# SCH_Motor-Driver-Pcb_2024-06-14.net
KiCad netlist of a schematic drawn in EasyEDA
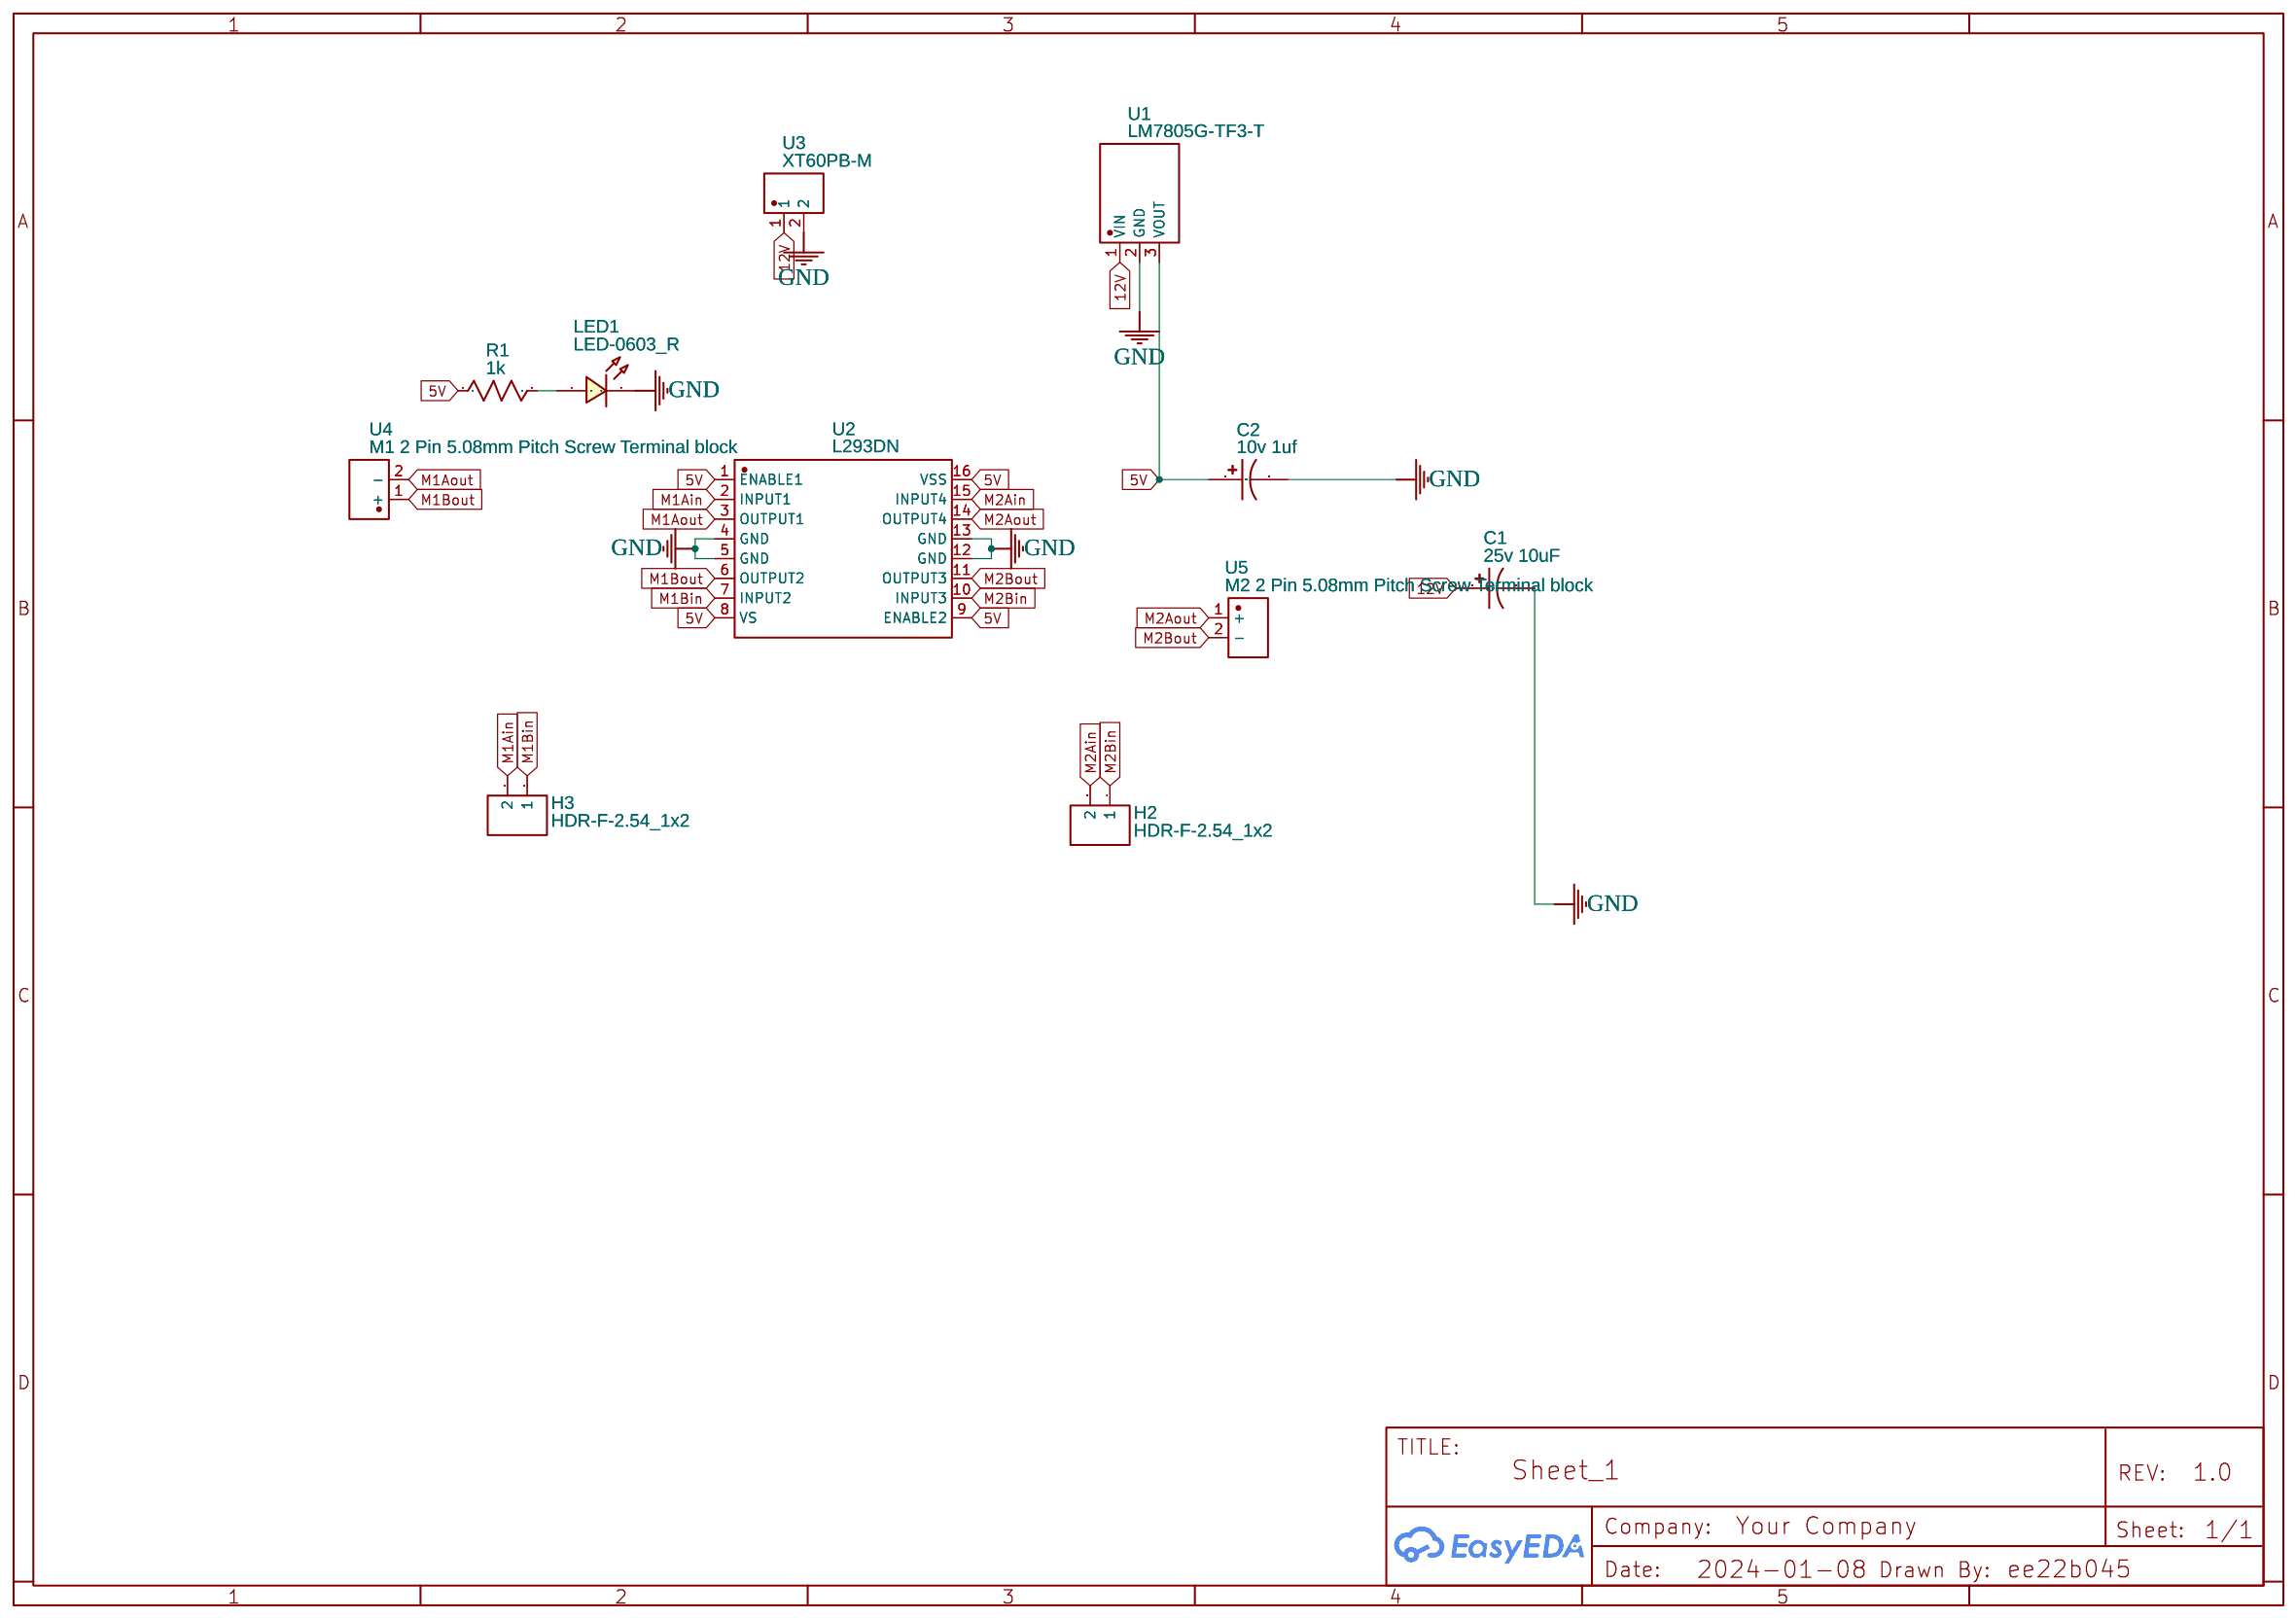
[diagram p0: schematic sheet]

(export (version "E")
  (design (tool "Eeschema 10.0.6"))
  (components
    (comp (ref "C1") (value "25v 10uF") (libsource (lib "") (part "C_Tan_SMD_A_US")))
    (comp (ref "C2") (value "10v 1uf") (libsource (lib "") (part "C_Tan_SMD_A_US")))
    (comp (ref "H2") (value "HDR-F-2.54_1x2") (libsource (lib "") (part "HDR-F-2.54_1x2")))
    (comp (ref "H3") (value "HDR-F-2.54_1x2") (libsource (lib "") (part "HDR-F-2.54_1x2")))
    (comp (ref "LED1")
      (value "LED-0603_R")
      (fields
        (field (name "Manufacturer Part") "19-217/R6C-AL1M2VY/3T")
        (field (name "Manufacturer") "EVERLIGHT(台湾亿光)")
      )
      (libsource (lib "") (part "LED-0603_R"))
    )
    (comp (ref "R1") (value "1k") (libsource (lib "") (part "R_0603_US")))
    (comp (ref "U1")
      (value "LM7805G-TF3-T")
      (fields (field (name "Manufacturer") "UTC(友顺)"))
      (libsource (lib "") (part "LM7805G-TF3-T"))
    )
    (comp (ref "U2")
      (value "L293DN")
      (fields (field (name "Manufacturer") "HGSEMI"))
      (libsource (lib "") (part "L293DN"))
    )
    (comp (ref "U3") (value "XT60PB-M") (libsource (lib "") (part "XT60PB-M")))
    (comp (ref "U4")
      (value "M1 2 Pin 5.08mm Pitch Screw Terminal block")
      (libsource (lib "") (part "2 Pin 5.08mm Pitch Screw Terminal block"))
    )
    (comp (ref "U5")
      (value "M2 2 Pin 5.08mm Pitch Screw Terminal block")
      (libsource (lib "") (part "2 Pin 5.08mm Pitch Screw Terminal block_1"))
    )
  )
  (nets
    (net (code "1") (name "5V") (class "Default")
      (node (ref "C2") (pin "1") (pinfunction "1_1") (pintype "unspecified"))
      (node (ref "R1") (pin "1") (pinfunction "1_1") (pintype "unspecified"))
      (node (ref "U1") (pin "3") (pinfunction "VOUT_3") (pintype "unspecified"))
      (node (ref "U2") (pin "1") (pinfunction "ENABLE1_1") (pintype "unspecified"))
      (node (ref "U2") (pin "16") (pinfunction "VSS_16") (pintype "unspecified"))
      (node (ref "U2") (pin "8") (pinfunction "VS_8") (pintype "unspecified"))
      (node (ref "U2") (pin "9") (pinfunction "ENABLE2_9") (pintype "unspecified"))
    )
    (net (code "2") (name "12V") (class "Default")
      (node (ref "C1") (pin "1") (pinfunction "1_1") (pintype "unspecified"))
      (node (ref "U1") (pin "1") (pinfunction "VIN_1") (pintype "unspecified"))
      (node (ref "U3") (pin "1") (pinfunction "1_1") (pintype "unspecified"))
    )
    (net (code "3") (name "GND") (class "Default")
      (node (ref "C1") (pin "2") (pinfunction "2_2") (pintype "unspecified"))
      (node (ref "C2") (pin "2") (pinfunction "2_2") (pintype "unspecified"))
      (node (ref "LED1") (pin "2") (pinfunction "2_2") (pintype "unspecified"))
      (node (ref "U1") (pin "2") (pinfunction "GND_2") (pintype "unspecified"))
      (node (ref "U2") (pin "12") (pinfunction "GND_12") (pintype "unspecified"))
      (node (ref "U2") (pin "13") (pinfunction "GND_13") (pintype "unspecified"))
      (node (ref "U2") (pin "4") (pinfunction "GND_4") (pintype "unspecified"))
      (node (ref "U2") (pin "5") (pinfunction "GND_5") (pintype "unspecified"))
      (node (ref "U3") (pin "2") (pinfunction "2_2") (pintype "unspecified"))
    )
    (net (code "4") (name "M1Ain") (class "Default")
      (node (ref "H3") (pin "2") (pinfunction "2_2") (pintype "input"))
      (node (ref "U2") (pin "2") (pinfunction "INPUT1_2") (pintype "unspecified"))
    )
    (net (code "5") (name "M1Aout") (class "Default")
      (node (ref "U2") (pin "3") (pinfunction "OUTPUT1_3") (pintype "unspecified"))
      (node (ref "U4") (pin "2") (pinfunction "-_2") (pintype "unspecified"))
    )
    (net (code "6") (name "M1Bin") (class "Default")
      (node (ref "H3") (pin "1") (pinfunction "1_1") (pintype "input"))
      (node (ref "U2") (pin "7") (pinfunction "INPUT2_7") (pintype "unspecified"))
    )
    (net (code "7") (name "M1Bout") (class "Default")
      (node (ref "U2") (pin "6") (pinfunction "OUTPUT2_6") (pintype "unspecified"))
      (node (ref "U4") (pin "1") (pinfunction "+_1") (pintype "unspecified"))
    )
    (net (code "8") (name "M2Ain") (class "Default")
      (node (ref "H2") (pin "2") (pinfunction "2_2") (pintype "input"))
      (node (ref "U2") (pin "15") (pinfunction "INPUT4_15") (pintype "unspecified"))
    )
    (net (code "9") (name "M2Aout") (class "Default")
      (node (ref "U2") (pin "14") (pinfunction "OUTPUT4_14") (pintype "unspecified"))
      (node (ref "U5") (pin "1") (pinfunction "+_1") (pintype "unspecified"))
    )
    (net (code "10") (name "M2Bin") (class "Default")
      (node (ref "H2") (pin "1") (pinfunction "1_1") (pintype "input"))
      (node (ref "U2") (pin "10") (pinfunction "INPUT3_10") (pintype "unspecified"))
    )
    (net (code "11") (name "M2Bout") (class "Default")
      (node (ref "U2") (pin "11") (pinfunction "OUTPUT3_11") (pintype "unspecified"))
      (node (ref "U5") (pin "2") (pinfunction "-_2") (pintype "unspecified"))
    )
    (net (code "12") (name "Net-(LED1-Pad1)") (class "Default")
      (node (ref "LED1") (pin "1") (pinfunction "1_1") (pintype "unspecified"))
      (node (ref "R1") (pin "2") (pinfunction "2_2") (pintype "unspecified"))
    )
  )
)
